# SparkFun_LilyPad_Tricolor-LED.net
KiCad netlist of a schematic drawn in EAGLE
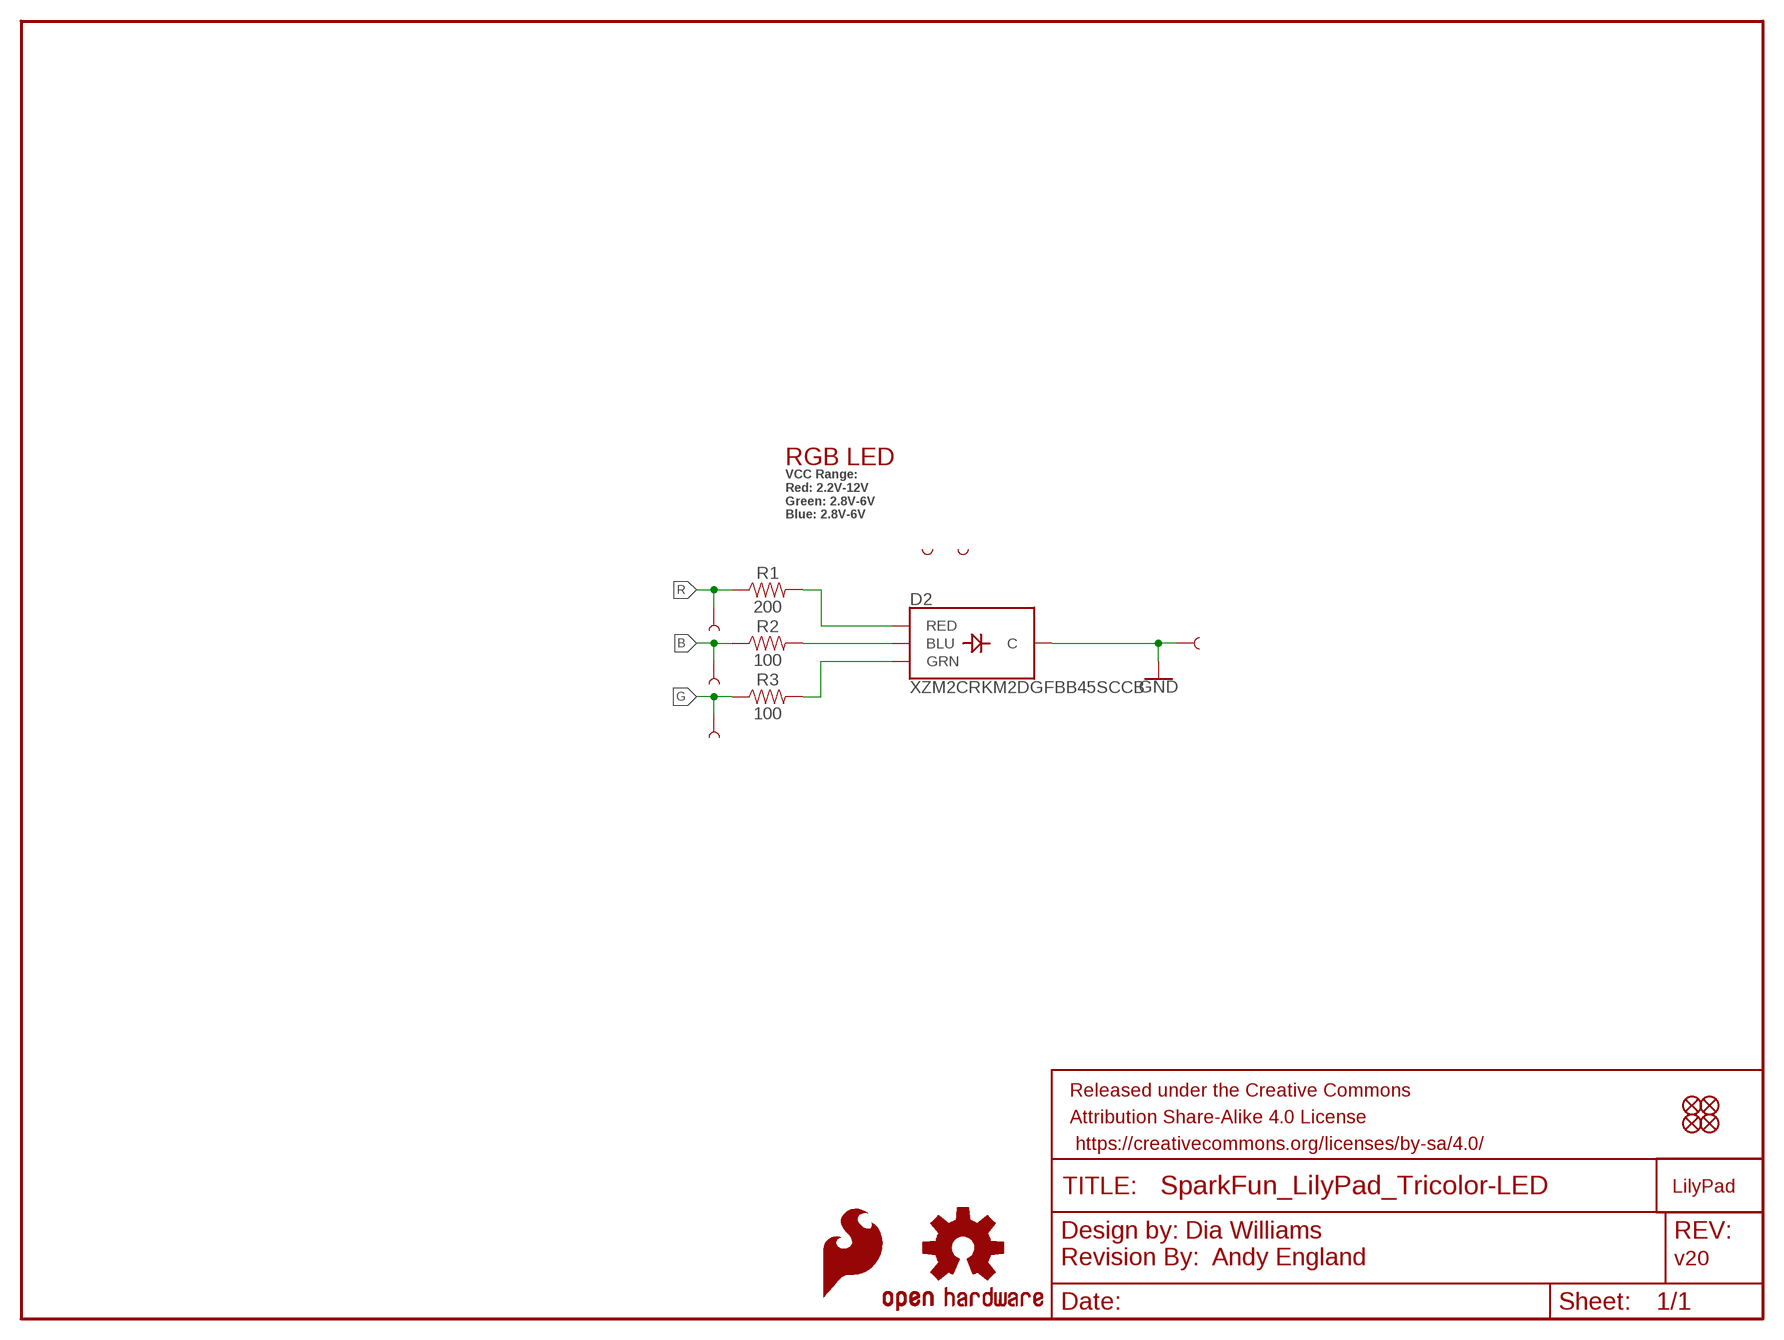
[diagram p0: schematic, sheet 1]

(export (version "E")
  (design (tool "Eeschema 10.0.6"))
  (components
    (comp (ref "D2")
      (value "XZM2CRKM2DGFBB45SCCB")
      (footprint "eagle-import:PLCC4SMDLED")
      (libsource (lib "eagle-import") (part "SUNLEDSMD1"))
    )
    (comp (ref "FD1")
      (value "FIDUCIAL1X2")
      (footprint "eagle-import:FIDUCIAL-1X2")
      (libsource (lib "eagle-import") (part "FIDUCIAL1X2"))
    )
    (comp (ref "FD2")
      (value "FIDUCIAL1X2")
      (footprint "eagle-import:FIDUCIAL-1X2")
      (libsource (lib "eagle-import") (part "FIDUCIAL1X2"))
    )
    (comp (ref "FD3")
      (value "FIDUCIAL1X2")
      (footprint "eagle-import:FIDUCIAL-1X2")
      (libsource (lib "eagle-import") (part "FIDUCIAL1X2"))
    )
    (comp (ref "FD4")
      (value "FIDUCIAL1X2")
      (footprint "eagle-import:FIDUCIAL-1X2")
      (libsource (lib "eagle-import") (part "FIDUCIAL1X2"))
    )
    (comp (ref "FRAME1")
      (value "FRAME-LETTER")
      (footprint "eagle-import:CREATIVE_COMMONS")
      (libsource (lib "eagle-import") (part "FRAME-LETTER"))
    )
    (comp (ref "LOGO1")
      (value "REVISION")
      (footprint "eagle-import:REVISION")
      (libsource (lib "eagle-import") (part "REVISION"))
    )
    (comp (ref "LOGO2")
      (value "OSHW-LOGOS")
      (footprint "eagle-import:OSHW-LOGO-S")
      (libsource (lib "eagle-import") (part "OSHW-LOGOS"))
    )
    (comp (ref "LOGO3")
      (value "SFE_LOGO_FLAME.1_INCH")
      (footprint "eagle-import:SFE_LOGO_FLAME_.1")
      (libsource (lib "eagle-import") (part "SFE_LOGO_FLAME.1_INCH"))
    )
    (comp (ref "R1")
      (value "200")
      (footprint "eagle-import:0603")
      (libsource (lib "eagle-import") (part "200OHM-0603-1/10W-1%"))
    )
    (comp (ref "R2")
      (value "100")
      (footprint "eagle-import:0603")
      (libsource (lib "eagle-import") (part "100OHM-0603-1/10W-1%"))
    )
    (comp (ref "R3")
      (value "100")
      (footprint "eagle-import:0603")
      (libsource (lib "eagle-import") (part "100OHM-0603-1/10W-1%"))
    )
    (comp (ref "U$1")
      (value "LOGO-LPLP")
      (footprint "eagle-import:LOGO-LILYPAD")
      (libsource (lib "eagle-import") (part "LOGO-LPLP"))
    )
    (comp (ref "U$2")
      (value "SEWTAP-NOHOLE2")
      (footprint "eagle-import:PETAL-NOHOLE-2SIDE")
      (libsource (lib "eagle-import") (part "SEWTAP-NOHOLE2"))
    )
    (comp (ref "U$3")
      (value "SEWTAP-NOHOLE2")
      (footprint "eagle-import:PETAL-NOHOLE-2SIDE")
      (libsource (lib "eagle-import") (part "SEWTAP-NOHOLE2"))
    )
    (comp (ref "U$7")
      (value "SEWTAP6")
      (footprint "eagle-import:PETAL-SMALL-2SIDE")
      (libsource (lib "eagle-import") (part "SEWTAP6"))
    )
    (comp (ref "U$8")
      (value "SEWTAP6")
      (footprint "eagle-import:PETAL-SMALL-2SIDE")
      (libsource (lib "eagle-import") (part "SEWTAP6"))
    )
    (comp (ref "U$9")
      (value "SEWTAP6")
      (footprint "eagle-import:PETAL-SMALL-2SIDE")
      (libsource (lib "eagle-import") (part "SEWTAP6"))
    )
    (comp (ref "U$10")
      (value "SEWTAP6")
      (footprint "eagle-import:PETAL-SMALL-2SIDE")
      (libsource (lib "eagle-import") (part "SEWTAP6"))
    )
  )
  (nets
    (net (code "1") (name "B") (class "Default")
      (node (ref "R2") (pin "1") (pinfunction "1_1") (pintype "passive"))
      (node (ref "U$9") (pin "1") (pinfunction "1_1") (pintype "bidirectional"))
    )
    (net (code "2") (name "G") (class "Default")
      (node (ref "R3") (pin "1") (pinfunction "1_1") (pintype "passive"))
      (node (ref "U$8") (pin "1") (pinfunction "1_1") (pintype "bidirectional"))
    )
    (net (code "3") (name "GND") (class "Default")
      (node (ref "D2") (pin "4") (pinfunction "C_4") (pintype "bidirectional"))
      (node (ref "U$10") (pin "1") (pinfunction "1_1") (pintype "bidirectional"))
    )
    (net (code "4") (name "Net-(D2-BLU)") (class "Default")
      (node (ref "D2") (pin "3") (pinfunction "BLU_3") (pintype "bidirectional"))
      (node (ref "R2") (pin "2") (pinfunction "2_2") (pintype "passive"))
    )
    (net (code "5") (name "Net-(D2-GRN)") (class "Default")
      (node (ref "D2") (pin "2") (pinfunction "GRN_2") (pintype "bidirectional"))
      (node (ref "R3") (pin "2") (pinfunction "2_2") (pintype "passive"))
    )
    (net (code "6") (name "Net-(D2-RED)") (class "Default")
      (node (ref "D2") (pin "1") (pinfunction "RED_1") (pintype "bidirectional"))
      (node (ref "R1") (pin "2") (pinfunction "2_2") (pintype "passive"))
    )
    (net (code "7") (name "R") (class "Default")
      (node (ref "R1") (pin "1") (pinfunction "1_1") (pintype "passive"))
      (node (ref "U$7") (pin "1") (pinfunction "1_1") (pintype "bidirectional"))
    )
  )
)
